# Main_Circuit.net
KiCad netlist of a schematic drawn in Altium Designer
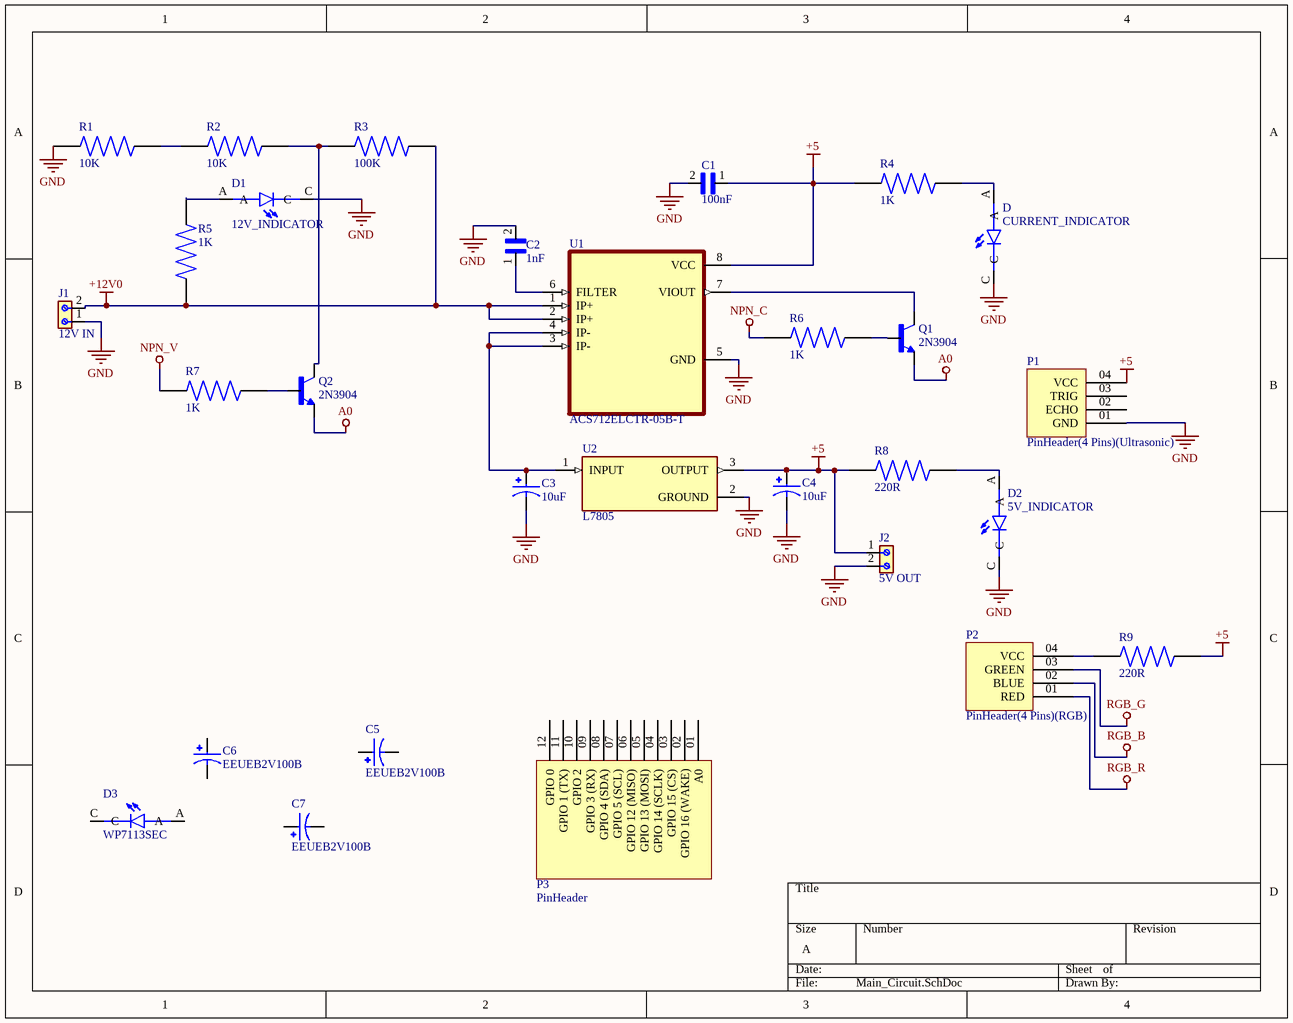
[diagram p0: Main_Circuit.SchDoc]

(export (version "E")
  (design (tool "Eeschema 10.0.6"))
  (components
    (comp (ref "C1")
      (value "100nF")
      (footprint "CAPRR508W50L508T318H762")
      (description "Cap Ceramic 0.1uF 100V X7R 10% Radial 5mm 125Â°C Bulk")
      (fields (field (name "MP") "FG24X7R2A104KNT00") (field (name "MF") "TDK"))
      (libsource (lib "") (part "FG24X7R2A104KNT00_1"))
    )
    (comp (ref "C2")
      (value "1nF")
      (footprint "CAPRR508W50L508T318H762")
      (description "Cap Ceramic 0.1uF 100V X7R 10% Radial 5mm 125Â°C Bulk")
      (fields (field (name "MP") "FG24X7R2A104KNT00") (field (name "MF") "TDK"))
      (libsource (lib "MegaProject_Lib") (part "FG24X7R2A104KNT00"))
    )
    (comp (ref "C3")
      (value "10uF")
      (footprint "CAPPRD500W60D1000H2000")
      (description "Aluminum Electrolytic Capacitors - Radial Leaded 10uF 350volts AEC-Q200")
      (fields (field (name "MF") "Panasonic") (field (name "MP") "EEU-EB2V100B"))
      (libsource (lib "MegaProject_Lib") (part "EEUEB2V100B"))
    )
    (comp (ref "C4")
      (value "10uF")
      (footprint "CAPPRD500W60D1000H2000")
      (description "Aluminum Electrolytic Capacitors - Radial Leaded 10uF 350volts AEC-Q200")
      (fields (field (name "MF") "Panasonic") (field (name "MP") "EEU-EB2V100B"))
      (libsource (lib "MegaProject_Lib") (part "EEUEB2V100B"))
    )
    (comp (ref "C5")
      (value "EEUEB2V100B")
      (footprint "CAPPRD500W60D1000H2000")
      (description "Aluminum Electrolytic Capacitors - Radial Leaded 10uF 350volts AEC-Q200")
      (fields (field (name "MF") "Panasonic") (field (name "MP") "EEU-EB2V100B"))
      (libsource (lib "") (part "EEUEB2V100B_1"))
    )
    (comp (ref "C6")
      (value "EEUEB2V100B")
      (footprint "CAPPRD500W60D1000H2000")
      (description "Aluminum Electrolytic Capacitors - Radial Leaded 10uF 350volts AEC-Q200")
      (fields (field (name "MF") "Panasonic") (field (name "MP") "EEU-EB2V100B"))
      (libsource (lib "MegaProject_Lib") (part "EEUEB2V100B"))
    )
    (comp (ref "C7")
      (value "EEUEB2V100B")
      (footprint "CAPPRD500W60D1000H2000")
      (description "Aluminum Electrolytic Capacitors - Radial Leaded 10uF 350volts AEC-Q200")
      (fields (field (name "MF") "Panasonic") (field (name "MP") "EEU-EB2V100B"))
      (libsource (lib "") (part "EEUEB2V100B_1"))
    )
    (comp (ref "D")
      (value "CURRENT_INDICATOR")
      (footprint "LED_WP7113SEC")
      (description "Red 625nm LED Indication - Discrete 2.2V Radial")
      (fields (field (name "MF") "Kingbright") (field (name "MP") "WP7113SEC"))
      (libsource (lib "MegaProject_Lib") (part "WP7113SEC"))
    )
    (comp (ref "D1")
      (value "12V_INDICATOR")
      (footprint "LED_WP7113SEC")
      (description "Red 625nm LED Indication - Discrete 2.2V Radial")
      (fields (field (name "MF") "Kingbright") (field (name "MP") "WP7113SEC"))
      (libsource (lib "MegaProject_Lib") (part "WP7113SEC"))
    )
    (comp (ref "D2")
      (value "5V_INDICATOR")
      (footprint "LED_WP7113SEC")
      (description "Red 625nm LED Indication - Discrete 2.2V Radial")
      (fields (field (name "MF") "Kingbright") (field (name "MP") "WP7113SEC"))
      (libsource (lib "MegaProject_Lib") (part "WP7113SEC"))
    )
    (comp (ref "D3")
      (value "WP7113SEC")
      (footprint "LED_WP7113SEC")
      (description "Red 625nm LED Indication - Discrete 2.2V Radial")
      (fields (field (name "MF") "Kingbright"))
      (libsource (lib "MegaProject_Lib") (part "WP7113SEC"))
    )
    (comp (ref "J1")
      (value "12V IN")
      (footprint "691253410002")
      (description "7.62 MM TERMINAL BLOCK, HORIZONT")
      (fields (field (name "MF") "WÃ¼rth Elektronik") (field (name "MP") "691253410002"))
      (libsource (lib "MegaProject_Lib") (part "691253410002"))
    )
    (comp (ref "J2")
      (value "5V OUT")
      (footprint "691253410002")
      (description "7.62 MM TERMINAL BLOCK, HORIZONT")
      (fields (field (name "MF") "WÃ¼rth Elektronik") (field (name "MP") "691253410002"))
      (libsource (lib "") (part "691253410002_1"))
    )
    (comp (ref "P1")
      (value "PinHeader(4 Pins)(Ultrasonic)")
      (footprint "4 pins connector")
      (libsource (lib "MegaProject_Lib") (part "PinHeader(4 Pins)(Ultrasonic)"))
    )
    (comp (ref "P2")
      (value "PinHeader(4 Pins)(RGB)")
      (footprint "4 pins connector")
      (libsource (lib "MegaProject_Lib") (part "PinHeader(4 Pins)(RGB)"))
    )
    (comp (ref "P3")
      (value "PinHeader")
      (footprint "12 pins connector")
      (libsource (lib "MegaProject_Lib") (part "PinHeader"))
    )
    (comp (ref "Q1")
      (value "2N3904")
      (footprint "TO92127P495H495-3")
      (description "TRANS NPN 40V 200MA TO92-3")
      (fields (field (name "MF") "Rectron"))
      (libsource (lib "MegaProject_Lib") (part "2N3904"))
    )
    (comp (ref "Q2")
      (value "2N3904")
      (footprint "TO92127P495H495-3")
      (description "TRANS NPN 40V 200MA TO92-3")
      (fields (field (name "MF") "Rectron"))
      (libsource (lib "MegaProject_Lib") (part "2N3904"))
    )
    (comp (ref "R1")
      (value "10K")
      (footprint "RESAD1100W55L680D260")
      (description "RES 280K OHM 1/4W 1% AXIAL")
      (fields (field (name "MP") "MFR-25FBF52-3K16"))
      (libsource (lib "MegaProject_Lib") (part "MFR-25FBF52-3K16"))
    )
    (comp (ref "R2")
      (value "10K")
      (footprint "RESAD1100W55L680D260")
      (description "RES 280K OHM 1/4W 1% AXIAL")
      (fields (field (name "MP") "MFR-25FBF52-3K16"))
      (libsource (lib "MegaProject_Lib") (part "MFR-25FBF52-3K16"))
    )
    (comp (ref "R3")
      (value "100K")
      (footprint "RESAD1100W55L680D260")
      (description "RES 280K OHM 1/4W 1% AXIAL")
      (fields (field (name "MP") "MFR-25FBF52-3K16"))
      (libsource (lib "MegaProject_Lib") (part "MFR-25FBF52-3K16"))
    )
    (comp (ref "R4")
      (value "1K")
      (footprint "RESAD1100W55L680D260")
      (description "RES 280K OHM 1/4W 1% AXIAL")
      (fields (field (name "MP") "MFR-25FBF52-3K16"))
      (libsource (lib "MegaProject_Lib") (part "MFR-25FBF52-3K16"))
    )
    (comp (ref "R5")
      (value "1K")
      (footprint "RESAD1100W55L680D260")
      (description "RES 280K OHM 1/4W 1% AXIAL")
      (fields (field (name "MP") "MFR-25FBF52-3K16"))
      (libsource (lib "MegaProject_Lib") (part "MFR-25FBF52-3K16"))
    )
    (comp (ref "R6")
      (value "1K")
      (footprint "RESAD1100W55L680D260")
      (description "RES 280K OHM 1/4W 1% AXIAL")
      (fields (field (name "MP") "MFR-25FBF52-3K16"))
      (libsource (lib "MegaProject_Lib") (part "MFR-25FBF52-3K16"))
    )
    (comp (ref "R7")
      (value "1K")
      (footprint "RESAD1100W55L680D260")
      (description "RES 280K OHM 1/4W 1% AXIAL")
      (fields (field (name "MP") "MFR-25FBF52-3K16"))
      (libsource (lib "MegaProject_Lib") (part "MFR-25FBF52-3K16"))
    )
    (comp (ref "R8")
      (value "220R")
      (footprint "RESAD1100W55L680D260")
      (description "RES 280K OHM 1/4W 1% AXIAL")
      (fields (field (name "MP") "MFR-25FBF52-3K16"))
      (libsource (lib "MegaProject_Lib") (part "MFR-25FBF52-3K16"))
    )
    (comp (ref "R9")
      (value "220R")
      (footprint "RESAD1100W55L680D260")
      (description "RES 280K OHM 1/4W 1% AXIAL")
      (fields (field (name "MP") "MFR-25FBF52-3K16"))
      (libsource (lib "MegaProject_Lib") (part "MFR-25FBF52-3K16"))
    )
    (comp (ref "U1")
      (value "ACS712ELCTR-05B-T")
      (footprint "SOIC127P600X175-8N - duplicate")
      (description "Current Sensor 5A 1 Channel Hall Effect, Open Loop Bidirectional 8-SOIC (0.154, 3.90mm Width)")
      (fields (field (name "MF") "Allegro MicroSystems LLC"))
      (libsource (lib "MegaProject_Lib") (part "ACS712ELCTR-05B-T"))
    )
    (comp (ref "U2")
      (value "L7805")
      (footprint "TO255P1020X450X2000-3")
      (description "Standard Regulator Pos 5V 1.5A 3-Pin(3+Tab) TO-220FP Tube")
      (fields (field (name "MF") "STMicroelectronics"))
      (libsource (lib "MegaProject_Lib") (part "L7805"))
    )
  )
  (nets
    (net (code "1") (name "+5") (class "Default")
      (node (ref "C1") (pin "1") (pinfunction "1_1") (pintype "passive"))
      (node (ref "C4") (pin "P") (pinfunction "P_P") (pintype "passive"))
      (node (ref "J2") (pin "1") (pinfunction "1_1") (pintype "passive"))
      (node (ref "P1") (pin "04") (pinfunction "VCC_04") (pintype "passive"))
      (node (ref "R4") (pin "1") (pinfunction "1_1") (pintype "passive"))
      (node (ref "R8") (pin "2") (pinfunction "2_2") (pintype "passive"))
      (node (ref "R9") (pin "1") (pinfunction "1_1") (pintype "passive"))
      (node (ref "U1") (pin "8") (pinfunction "VCC_8") (pintype "power_in"))
      (node (ref "U2") (pin "3") (pinfunction "OUTPUT_3") (pintype "output"))
    )
    (net (code "2") (name "+12V0") (class "Default")
      (node (ref "J1") (pin "2") (pinfunction "2_2") (pintype "passive"))
      (node (ref "R3") (pin "2") (pinfunction "2_2") (pintype "passive"))
      (node (ref "R5") (pin "1") (pinfunction "1_1") (pintype "passive"))
      (node (ref "U1") (pin "1") (pinfunction "IP+_1") (pintype "input"))
      (node (ref "U1") (pin "2") (pinfunction "IP+_2") (pintype "input"))
    )
    (net (code "3") (name "A0") (class "Default")
      (node (ref "Q1") (pin "1") (pinfunction "E_1") (pintype "passive"))
      (node (ref "Q2") (pin "1") (pinfunction "E_1") (pintype "passive"))
    )
    (net (code "4") (name "GND") (class "Default")
      (node (ref "C1") (pin "2") (pinfunction "2_2") (pintype "passive"))
      (node (ref "C2") (pin "2") (pinfunction "2_2") (pintype "passive"))
      (node (ref "C3") (pin "N") (pinfunction "N_N") (pintype "passive"))
      (node (ref "C4") (pin "N") (pinfunction "N_N") (pintype "passive"))
      (node (ref "D") (pin "C") (pinfunction "C_C") (pintype "passive"))
      (node (ref "D1") (pin "C") (pinfunction "C_C") (pintype "passive"))
      (node (ref "D2") (pin "C") (pinfunction "C_C") (pintype "passive"))
      (node (ref "J1") (pin "1") (pinfunction "1_1") (pintype "passive"))
      (node (ref "J2") (pin "2") (pinfunction "2_2") (pintype "passive"))
      (node (ref "P1") (pin "01") (pinfunction "GND_01") (pintype "passive"))
      (node (ref "R1") (pin "1") (pinfunction "1_1") (pintype "passive"))
      (node (ref "U1") (pin "5") (pinfunction "GND_5") (pintype "power_in"))
      (node (ref "U2") (pin "2") (pinfunction "GROUND_2") (pintype "power_in"))
    )
    (net (code "5") (name "NPN_C") (class "Default")
      (node (ref "R6") (pin "1") (pinfunction "1_1") (pintype "passive"))
    )
    (net (code "6") (name "NPN_V") (class "Default")
      (node (ref "R7") (pin "1") (pinfunction "1_1") (pintype "passive"))
    )
    (net (code "7") (name "Net-(D-PadA)") (class "Default")
      (node (ref "D") (pin "A") (pinfunction "A_A") (pintype "passive"))
      (node (ref "R4") (pin "2") (pinfunction "2_2") (pintype "passive"))
    )
    (net (code "8") (name "Net-(D1-PadA)") (class "Default")
      (node (ref "D1") (pin "A") (pinfunction "A_A") (pintype "passive"))
      (node (ref "R5") (pin "2") (pinfunction "2_2") (pintype "passive"))
    )
    (net (code "9") (name "Net-(D2-PadA)") (class "Default")
      (node (ref "D2") (pin "A") (pinfunction "A_A") (pintype "passive"))
      (node (ref "R8") (pin "1") (pinfunction "1_1") (pintype "passive"))
    )
    (net (code "10") (name "Net-(P2-VCC)") (class "Default")
      (node (ref "P2") (pin "04") (pinfunction "VCC_04") (pintype "passive"))
      (node (ref "R9") (pin "2") (pinfunction "2_2") (pintype "passive"))
    )
    (net (code "11") (name "Net-(Q1-B)") (class "Default")
      (node (ref "Q1") (pin "2") (pinfunction "B_2") (pintype "passive"))
      (node (ref "R6") (pin "2") (pinfunction "2_2") (pintype "passive"))
    )
    (net (code "12") (name "Net-(Q1-C)") (class "Default")
      (node (ref "Q1") (pin "3") (pinfunction "C_3") (pintype "passive"))
      (node (ref "U1") (pin "7") (pinfunction "VIOUT_7") (pintype "output"))
    )
    (net (code "13") (name "Net-(Q2-B)") (class "Default")
      (node (ref "Q2") (pin "2") (pinfunction "B_2") (pintype "passive"))
      (node (ref "R7") (pin "2") (pinfunction "2_2") (pintype "passive"))
    )
    (net (code "14") (name "Net-(Q2-C)") (class "Default")
      (node (ref "Q2") (pin "3") (pinfunction "C_3") (pintype "passive"))
      (node (ref "R2") (pin "2") (pinfunction "2_2") (pintype "passive"))
      (node (ref "R3") (pin "1") (pinfunction "1_1") (pintype "passive"))
    )
    (net (code "15") (name "Net-(R1-Pad2)") (class "Default")
      (node (ref "R1") (pin "2") (pinfunction "2_2") (pintype "passive"))
      (node (ref "R2") (pin "1") (pinfunction "1_1") (pintype "passive"))
    )
    (net (code "16") (name "Net-(U1-FILTER)") (class "Default")
      (node (ref "C2") (pin "1") (pinfunction "1_1") (pintype "passive"))
      (node (ref "U1") (pin "6") (pinfunction "FILTER_6") (pintype "input"))
    )
    (net (code "17") (name "Net-(U2-INPUT)") (class "Default")
      (node (ref "C3") (pin "P") (pinfunction "P_P") (pintype "passive"))
      (node (ref "U1") (pin "3") (pinfunction "IP-_3") (pintype "input"))
      (node (ref "U1") (pin "4") (pinfunction "IP-_4") (pintype "input"))
      (node (ref "U2") (pin "1") (pinfunction "INPUT_1") (pintype "input"))
    )
    (net (code "18") (name "RGB_B") (class "Default")
      (node (ref "P2") (pin "02") (pinfunction "BLUE_02") (pintype "passive"))
    )
    (net (code "19") (name "RGB_G") (class "Default")
      (node (ref "P2") (pin "03") (pinfunction "GREEN_03") (pintype "passive"))
    )
    (net (code "20") (name "RGB_R") (class "Default")
      (node (ref "P2") (pin "01") (pinfunction "RED_01") (pintype "passive"))
    )
    (net (code "21") (name "unconnected-(C5-PadN)") (class "Default")
      (node (ref "C5") (pin "N") (pinfunction "N_N") (pintype "passive"))
    )
    (net (code "22") (name "unconnected-(C5-PadP)") (class "Default")
      (node (ref "C5") (pin "P") (pinfunction "P_P") (pintype "passive"))
    )
    (net (code "23") (name "unconnected-(C6-PadN)") (class "Default")
      (node (ref "C6") (pin "N") (pinfunction "N_N") (pintype "passive"))
    )
    (net (code "24") (name "unconnected-(C6-PadP)") (class "Default")
      (node (ref "C6") (pin "P") (pinfunction "P_P") (pintype "passive"))
    )
    (net (code "25") (name "unconnected-(C7-PadN)") (class "Default")
      (node (ref "C7") (pin "N") (pinfunction "N_N") (pintype "passive"))
    )
    (net (code "26") (name "unconnected-(C7-PadP)") (class "Default")
      (node (ref "C7") (pin "P") (pinfunction "P_P") (pintype "passive"))
    )
    (net (code "27") (name "unconnected-(D3-PadA)") (class "Default")
      (node (ref "D3") (pin "A") (pinfunction "A_A") (pintype "passive"))
    )
    (net (code "28") (name "unconnected-(D3-PadC)") (class "Default")
      (node (ref "D3") (pin "C") (pinfunction "C_C") (pintype "passive"))
    )
    (net (code "29") (name "unconnected-(P1-ECHO-Pad02)") (class "Default")
      (node (ref "P1") (pin "02") (pinfunction "ECHO_02") (pintype "passive"))
    )
    (net (code "30") (name "unconnected-(P1-TRIG-Pad03)") (class "Default")
      (node (ref "P1") (pin "03") (pinfunction "TRIG_03") (pintype "passive"))
    )
    (net (code "31") (name "unconnected-(P3-A0-Pad01)") (class "Default")
      (node (ref "P3") (pin "01") (pinfunction "A0_01") (pintype "passive"))
    )
    (net (code "32") (name "unconnected-(P3-GPIO_0-Pad12)") (class "Default")
      (node (ref "P3") (pin "12") (pinfunction "GPIO_0_12") (pintype "passive"))
    )
    (net (code "33") (name "unconnected-(P3-GPIO_1_(TX)-Pad11)") (class "Default")
      (node (ref "P3") (pin "11") (pinfunction "GPIO_1_(TX)_11") (pintype "passive"))
    )
    (net (code "34") (name "unconnected-(P3-GPIO_2-Pad10)") (class "Default")
      (node (ref "P3") (pin "10") (pinfunction "GPIO_2_10") (pintype "passive"))
    )
    (net (code "35") (name "unconnected-(P3-GPIO_3_(RX)-Pad09)") (class "Default")
      (node (ref "P3") (pin "09") (pinfunction "GPIO_3_(RX)_09") (pintype "passive"))
    )
    (net (code "36") (name "unconnected-(P3-GPIO_4_(SDA)-Pad08)") (class "Default")
      (node (ref "P3") (pin "08") (pinfunction "GPIO_4_(SDA)_08") (pintype "passive"))
    )
    (net (code "37") (name "unconnected-(P3-GPIO_5_(SCL)-Pad07)") (class "Default")
      (node (ref "P3") (pin "07") (pinfunction "GPIO_5_(SCL)_07") (pintype "passive"))
    )
    (net (code "38") (name "unconnected-(P3-GPIO_12_(MISO)-Pad06)") (class "Default")
      (node (ref "P3") (pin "06") (pinfunction "GPIO_12_(MISO)_06") (pintype "passive"))
    )
    (net (code "39") (name "unconnected-(P3-GPIO_13_(MOSI)-Pad05)") (class "Default")
      (node (ref "P3") (pin "05") (pinfunction "GPIO_13_(MOSI)_05") (pintype "passive"))
    )
    (net (code "40") (name "unconnected-(P3-GPIO_14_(SCLK)-Pad04)") (class "Default")
      (node (ref "P3") (pin "04") (pinfunction "GPIO_14_(SCLK)_04") (pintype "passive"))
    )
    (net (code "41") (name "unconnected-(P3-GPIO_15_(CS)-Pad03)") (class "Default")
      (node (ref "P3") (pin "03") (pinfunction "GPIO_15_(CS)_03") (pintype "passive"))
    )
    (net (code "42") (name "unconnected-(P3-GPIO_16_(WAKE)-Pad02)") (class "Default")
      (node (ref "P3") (pin "02") (pinfunction "GPIO_16_(WAKE)_02") (pintype "passive"))
    )
  )
)
